# OBCComms.net
KiCad netlist of a schematic drawn in Altium Designer
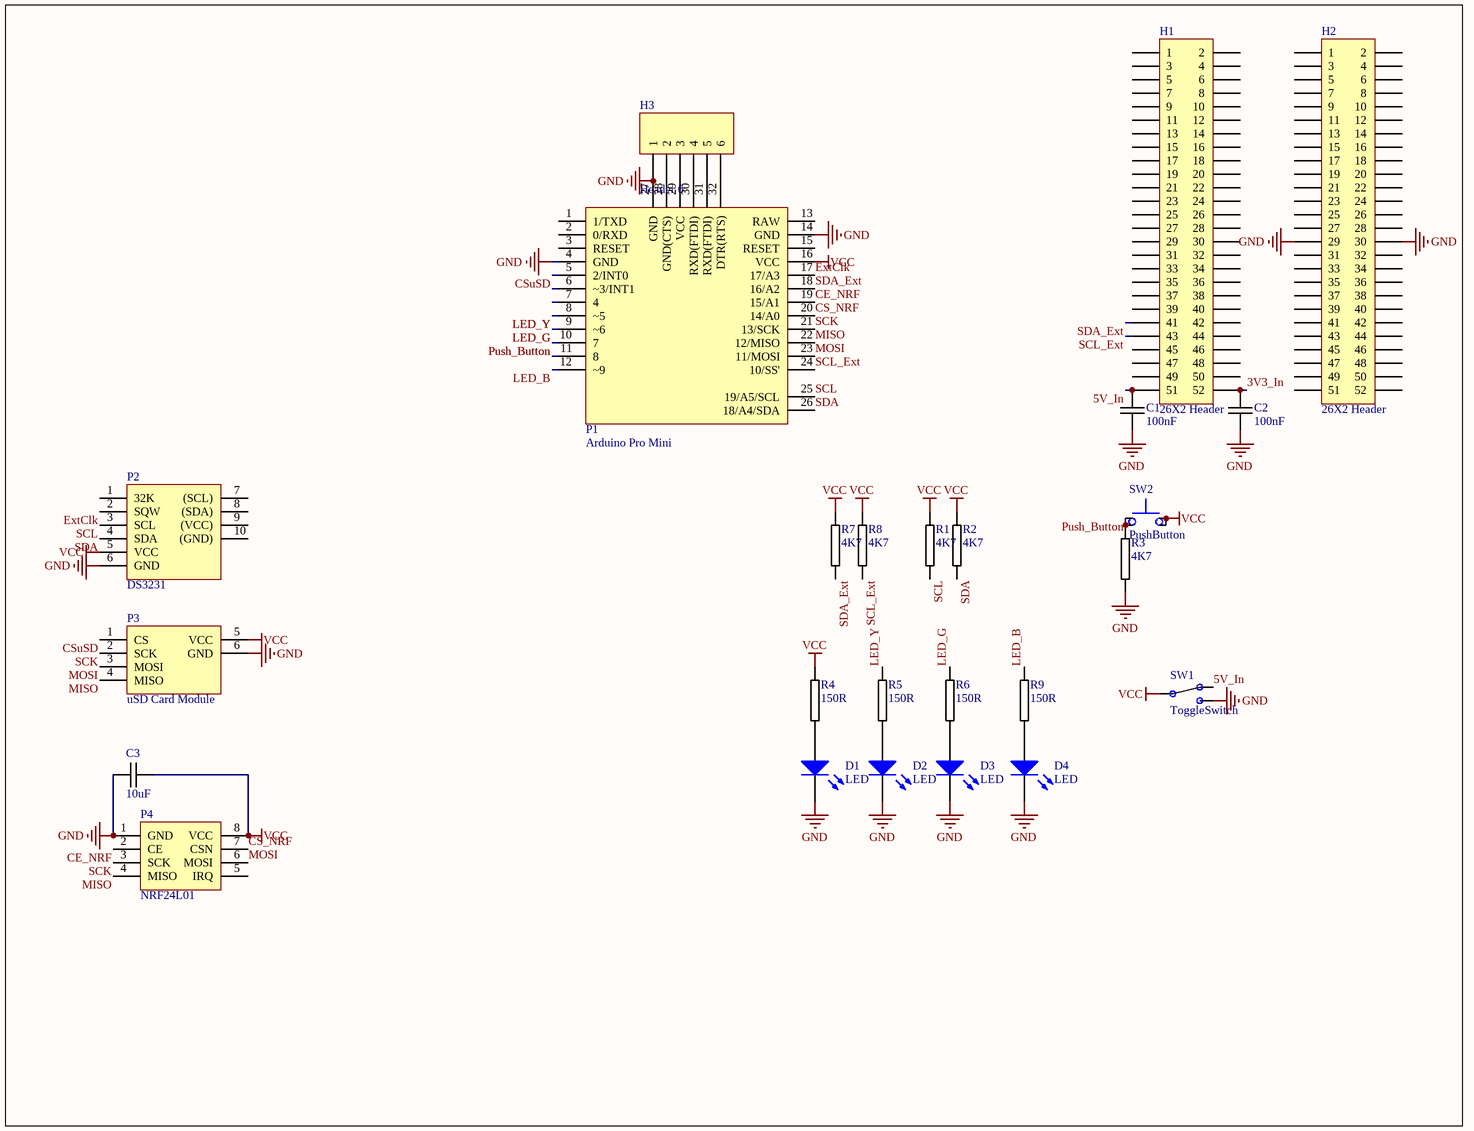
[diagram p0: OBCComms.SchDoc]

(export (version "E")
  (design (tool "Eeschema 10.0.6"))
  (components
    (comp (ref "C1")
      (value "100nF")
      (footprint "0805C-TBD")
      (description "CAPACITOR 0805 CERAMIC")
      (libsource (lib "vh_altium_library") (part "0805C-100nF-25V-X7R-MUR"))
    )
    (comp (ref "C2")
      (value "100nF")
      (footprint "0805C-TBD")
      (description "CAPACITOR 0805 CERAMIC")
      (libsource (lib "vh_altium_library") (part "0805C-100nF-25V-X7R-MUR"))
    )
    (comp (ref "C3")
      (value "10uF")
      (footprint "0805C-GENERIC")
      (description "CAPACITOR 0805 CERAMIC")
      (fields
        (field (name "MANUFACTURER PART NUMBER") "C2012X5R1C106M")
        (field (name "MANUFACTURER") "TDK Corporation")
      )
      (libsource (lib "vh_altium_library") (part "0805C-10UF-16V-X5R-TDK"))
    )
    (comp (ref "D1")
      (value "LED")
      (footprint "LED")
      (description "Small LED")
      (libsource (lib "Components") (part "LED"))
    )
    (comp (ref "D2")
      (value "LED")
      (footprint "LED")
      (description "Small LED")
      (libsource (lib "Components") (part "LED"))
    )
    (comp (ref "D3")
      (value "LED")
      (footprint "LED")
      (description "Small LED")
      (libsource (lib "Components") (part "LED"))
    )
    (comp (ref "D4")
      (value "LED")
      (footprint "LED")
      (description "Small LED")
      (libsource (lib "Components") (part "LED"))
    )
    (comp (ref "H1")
      (value "26X2 Header")
      (footprint "26X2 Header")
      (libsource (lib "CustomParts") (part "26X2 Header"))
    )
    (comp (ref "H2")
      (value "26X2 Header")
      (footprint "26X2 Header")
      (libsource (lib "CustomParts") (part "26X2 Header"))
    )
    (comp (ref "H3")
      (value "Header 6")
      (footprint "HDR1X6")
      (description "Header, 6-Pin")
      (fields (field (name "PUBLISHER") "Altium Limited"))
      (libsource (lib "Miscellaneous Connectors") (part "Header 6"))
    )
    (comp (ref "P1")
      (value "Arduino Pro Mini")
      (footprint "Arduino Pro Mini")
      (libsource (lib "Components") (part "Arduino Pro Mini"))
    )
    (comp (ref "P2")
      (value "DS3231")
      (footprint "RTC")
      (description "RTC")
      (libsource (lib "Components") (part "DS3231"))
    )
    (comp (ref "P3")
      (value "uSD Card Module")
      (footprint "uSD Card Module")
      (libsource (lib "Components") (part "uSD Card Module"))
    )
    (comp (ref "P4")
      (value "NRF24L01")
      (footprint "NRF24L01")
      (description "Radio Transceiver")
      (libsource (lib "Components") (part "NRF24L01"))
    )
    (comp (ref "R1")
      (value "4K7")
      (footprint "0805R-4K7")
      (description "RESISTOR 0805 1/4 WATT THIN FILM")
      (libsource (lib "vh_altium_library") (part "0805R-4K7"))
    )
    (comp (ref "R2")
      (value "4K7")
      (footprint "0805R-4K7")
      (description "RESISTOR 0805 1/4 WATT THIN FILM")
      (libsource (lib "vh_altium_library") (part "0805R-4K7"))
    )
    (comp (ref "R3")
      (value "4K7")
      (footprint "0805R-4K7")
      (description "RESISTOR 0805 1/4 WATT THIN FILM")
      (libsource (lib "vh_altium_library") (part "0805R-4K7"))
    )
    (comp (ref "R4")
      (value "150R")
      (footprint "0805R-150")
      (description "RESISTOR 0805 1/4 WATT THIN FILM")
      (libsource (lib "vh_altium_library") (part "0805R-150"))
    )
    (comp (ref "R5")
      (value "150R")
      (footprint "0805R-150")
      (description "RESISTOR 0805 1/4 WATT THIN FILM")
      (libsource (lib "vh_altium_library") (part "0805R-150"))
    )
    (comp (ref "R6")
      (value "150R")
      (footprint "0805R-150")
      (description "RESISTOR 0805 1/4 WATT THIN FILM")
      (libsource (lib "vh_altium_library") (part "0805R-150"))
    )
    (comp (ref "R7")
      (value "4K7")
      (footprint "0805R-4K7")
      (description "RESISTOR 0805 1/4 WATT THIN FILM")
      (libsource (lib "vh_altium_library") (part "0805R-4K7"))
    )
    (comp (ref "R8")
      (value "4K7")
      (footprint "0805R-4K7")
      (description "RESISTOR 0805 1/4 WATT THIN FILM")
      (libsource (lib "vh_altium_library") (part "0805R-4K7"))
    )
    (comp (ref "R9")
      (value "150R")
      (footprint "0805R-150")
      (description "RESISTOR 0805 1/4 WATT THIN FILM")
      (libsource (lib "vh_altium_library") (part "0805R-150"))
    )
    (comp (ref "SW1")
      (value "ToggleSwitch")
      (footprint "SWITCHFOOTPRINT")
      (libsource (lib "SBv1Components") (part "ToggleSwitch"))
    )
    (comp (ref "SW2")
      (value "PushButton")
      (footprint "PushButton")
      (libsource (lib "SBv1Components") (part "PushButton"))
    )
  )
  (nets
    (net (code "1") (name "/3V3_In") (class "Default")
      (node (ref "C2") (pin "1") (pintype "passive"))
      (node (ref "H1") (pin "52") (pinfunction "52_52") (pintype "passive"))
    )
    (net (code "2") (name "/5V_In") (class "Default")
      (node (ref "C1") (pin "1") (pintype "passive"))
      (node (ref "H1") (pin "51") (pinfunction "51_51") (pintype "passive"))
      (node (ref "SW1") (pin "24") (pinfunction "24_24") (pintype "passive"))
    )
    (net (code "3") (name "/CE_NRF") (class "Default")
      (node (ref "P1") (pin "19") (pinfunction "15/A1_19") (pintype "passive"))
      (node (ref "P4") (pin "2") (pinfunction "CE_2") (pintype "passive"))
    )
    (net (code "4") (name "/CS_NRF") (class "Default")
      (node (ref "P1") (pin "20") (pinfunction "14/A0_20") (pintype "passive"))
      (node (ref "P4") (pin "7") (pinfunction "CSN_7") (pintype "passive"))
    )
    (net (code "5") (name "/CSuSD") (class "Default")
      (node (ref "P1") (pin "5") (pinfunction "2/INT0_5") (pintype "passive"))
      (node (ref "P3") (pin "1") (pinfunction "CS_1") (pintype "passive"))
    )
    (net (code "6") (name "/ExtClk") (class "Default")
      (node (ref "P1") (pin "17") (pinfunction "17/A3_17") (pintype "passive"))
      (node (ref "P2") (pin "2") (pinfunction "SQW_2") (pintype "passive"))
    )
    (net (code "7") (name "/LED_B") (class "Default")
      (node (ref "P1") (pin "12") (pinfunction "~9_12") (pintype "passive"))
      (node (ref "R9") (pin "1") (pintype "passive"))
    )
    (net (code "8") (name "/LED_G") (class "Default")
      (node (ref "P1") (pin "9") (pinfunction "~6_9") (pintype "passive"))
      (node (ref "R6") (pin "1") (pintype "passive"))
    )
    (net (code "9") (name "/LED_Y") (class "Default")
      (node (ref "P1") (pin "8") (pinfunction "~5_8") (pintype "passive"))
      (node (ref "R5") (pin "1") (pintype "passive"))
    )
    (net (code "10") (name "/MISO") (class "Default")
      (node (ref "P1") (pin "22") (pinfunction "12/MISO_22") (pintype "passive"))
      (node (ref "P3") (pin "4") (pinfunction "MISO_4") (pintype "passive"))
      (node (ref "P4") (pin "4") (pinfunction "MISO_4") (pintype "passive"))
    )
    (net (code "11") (name "/MOSI") (class "Default")
      (node (ref "P1") (pin "23") (pinfunction "11/MOSI_23") (pintype "passive"))
      (node (ref "P3") (pin "3") (pinfunction "MOSI_3") (pintype "passive"))
      (node (ref "P4") (pin "6") (pinfunction "MOSI_6") (pintype "passive"))
    )
    (net (code "12") (name "/Push_Button") (class "Default")
      (node (ref "P1") (pin "10") (pinfunction "7_10") (pintype "passive"))
      (node (ref "R3") (pin "1") (pintype "passive"))
      (node (ref "SW2") (pin "26") (pinfunction "26_26") (pintype "passive"))
      (node (ref "SW2") (pin "28") (pinfunction "28_28") (pintype "passive"))
    )
    (net (code "13") (name "/SCK") (class "Default")
      (node (ref "P1") (pin "21") (pinfunction "13/SCK_21") (pintype "passive"))
      (node (ref "P3") (pin "2") (pinfunction "SCK_2") (pintype "passive"))
      (node (ref "P4") (pin "3") (pinfunction "SCK_3") (pintype "passive"))
    )
    (net (code "14") (name "/SCL") (class "Default")
      (node (ref "P1") (pin "25") (pinfunction "19/A5/SCL_25") (pintype "passive"))
      (node (ref "P2") (pin "3") (pinfunction "SCL_3") (pintype "passive"))
      (node (ref "R1") (pin "2") (pintype "passive"))
    )
    (net (code "15") (name "/SCL_Ext") (class "Default")
      (node (ref "H1") (pin "43") (pinfunction "43_43") (pintype "passive"))
      (node (ref "P1") (pin "24") (pinfunction "10/SS'_24") (pintype "passive"))
      (node (ref "R8") (pin "2") (pintype "passive"))
    )
    (net (code "16") (name "/SDA") (class "Default")
      (node (ref "P1") (pin "26") (pinfunction "18/A4/SDA_26") (pintype "passive"))
      (node (ref "P2") (pin "4") (pinfunction "SDA_4") (pintype "passive"))
      (node (ref "R2") (pin "2") (pintype "passive"))
    )
    (net (code "17") (name "/SDA_Ext") (class "Default")
      (node (ref "H1") (pin "41") (pinfunction "41_41") (pintype "passive"))
      (node (ref "P1") (pin "18") (pinfunction "16/A2_18") (pintype "passive"))
      (node (ref "R7") (pin "2") (pintype "passive"))
    )
    (net (code "18") (name "GND") (class "Default")
      (node (ref "C1") (pin "2") (pintype "passive"))
      (node (ref "C2") (pin "2") (pintype "passive"))
      (node (ref "C3") (pin "1") (pintype "passive"))
      (node (ref "D1") (pin "2") (pinfunction "K_2") (pintype "passive"))
      (node (ref "D2") (pin "2") (pinfunction "K_2") (pintype "passive"))
      (node (ref "D3") (pin "2") (pinfunction "K_2") (pintype "passive"))
      (node (ref "D4") (pin "2") (pinfunction "K_2") (pintype "passive"))
      (node (ref "H2") (pin "29") (pinfunction "29_29") (pintype "passive"))
      (node (ref "H2") (pin "30") (pinfunction "30_30") (pintype "passive"))
      (node (ref "H3") (pin "1") (pinfunction "1_1") (pintype "passive"))
      (node (ref "P1") (pin "14") (pinfunction "GND_14") (pintype "passive"))
      (node (ref "P1") (pin "27") (pinfunction "GND_27") (pintype "passive"))
      (node (ref "P1") (pin "4") (pinfunction "GND_4") (pintype "passive"))
      (node (ref "P2") (pin "6") (pinfunction "GND_6") (pintype "passive"))
      (node (ref "P3") (pin "6") (pinfunction "GND_6") (pintype "passive"))
      (node (ref "P4") (pin "1") (pinfunction "GND_1") (pintype "passive"))
      (node (ref "R3") (pin "2") (pintype "passive"))
      (node (ref "SW1") (pin "25") (pinfunction "25_25") (pintype "passive"))
    )
    (net (code "19") (name "Net-(D1-A)") (class "Default")
      (node (ref "D1") (pin "1") (pinfunction "A_1") (pintype "passive"))
      (node (ref "R4") (pin "2") (pintype "passive"))
    )
    (net (code "20") (name "Net-(D2-A)") (class "Default")
      (node (ref "D2") (pin "1") (pinfunction "A_1") (pintype "passive"))
      (node (ref "R5") (pin "2") (pintype "passive"))
    )
    (net (code "21") (name "Net-(D3-A)") (class "Default")
      (node (ref "D3") (pin "1") (pinfunction "A_1") (pintype "passive"))
      (node (ref "R6") (pin "2") (pintype "passive"))
    )
    (net (code "22") (name "Net-(D4-A)") (class "Default")
      (node (ref "D4") (pin "1") (pinfunction "A_1") (pintype "passive"))
      (node (ref "R9") (pin "2") (pintype "passive"))
    )
    (net (code "23") (name "Net-(H3-Pad3)") (class "Default")
      (node (ref "H3") (pin "3") (pinfunction "3_3") (pintype "passive"))
      (node (ref "P1") (pin "29") (pinfunction "VCC_29") (pintype "passive"))
    )
    (net (code "24") (name "Net-(H3-Pad4)") (class "Default")
      (node (ref "H3") (pin "4") (pinfunction "4_4") (pintype "passive"))
      (node (ref "P1") (pin "30") (pinfunction "RXD(FTDI)_30") (pintype "passive"))
    )
    (net (code "25") (name "Net-(H3-Pad5)") (class "Default")
      (node (ref "H3") (pin "5") (pinfunction "5_5") (pintype "passive"))
      (node (ref "P1") (pin "31") (pinfunction "RXD(FTDI)_31") (pintype "passive"))
    )
    (net (code "26") (name "Net-(P1-DTR(RTS))") (class "Default")
      (node (ref "H3") (pin "6") (pinfunction "6_6") (pintype "passive"))
      (node (ref "P1") (pin "32") (pinfunction "DTR(RTS)_32") (pintype "passive"))
    )
    (net (code "27") (name "Net-(P1-GND(CTS))") (class "Default")
      (node (ref "H3") (pin "2") (pinfunction "2_2") (pintype "passive"))
      (node (ref "P1") (pin "28") (pinfunction "GND(CTS)_28") (pintype "passive"))
    )
    (net (code "28") (name "VCC") (class "Default")
      (node (ref "C3") (pin "2") (pintype "passive"))
      (node (ref "P1") (pin "16") (pinfunction "VCC_16") (pintype "passive"))
      (node (ref "P2") (pin "5") (pinfunction "VCC_5") (pintype "passive"))
      (node (ref "P3") (pin "5") (pinfunction "VCC_5") (pintype "passive"))
      (node (ref "P4") (pin "8") (pinfunction "VCC_8") (pintype "passive"))
      (node (ref "R1") (pin "1") (pintype "passive"))
      (node (ref "R2") (pin "1") (pintype "passive"))
      (node (ref "R4") (pin "1") (pintype "passive"))
      (node (ref "R7") (pin "1") (pintype "passive"))
      (node (ref "R8") (pin "1") (pintype "passive"))
      (node (ref "SW1") (pin "23") (pinfunction "23_23") (pintype "passive"))
      (node (ref "SW2") (pin "27") (pinfunction "27_27") (pintype "passive"))
      (node (ref "SW2") (pin "29") (pinfunction "29_29") (pintype "passive"))
    )
    (net (code "29") (name "unconnected-(H1-Pad1)") (class "Default")
      (node (ref "H1") (pin "1") (pinfunction "1_1") (pintype "passive"))
    )
    (net (code "30") (name "unconnected-(H1-Pad2)") (class "Default")
      (node (ref "H1") (pin "2") (pinfunction "2_2") (pintype "passive"))
    )
    (net (code "31") (name "unconnected-(H1-Pad3)") (class "Default")
      (node (ref "H1") (pin "3") (pinfunction "3_3") (pintype "passive"))
    )
    (net (code "32") (name "unconnected-(H1-Pad4)") (class "Default")
      (node (ref "H1") (pin "4") (pinfunction "4_4") (pintype "passive"))
    )
    (net (code "33") (name "unconnected-(H1-Pad5)") (class "Default")
      (node (ref "H1") (pin "5") (pinfunction "5_5") (pintype "passive"))
    )
    (net (code "34") (name "unconnected-(H1-Pad6)") (class "Default")
      (node (ref "H1") (pin "6") (pinfunction "6_6") (pintype "passive"))
    )
    (net (code "35") (name "unconnected-(H1-Pad7)") (class "Default")
      (node (ref "H1") (pin "7") (pinfunction "7_7") (pintype "passive"))
    )
    (net (code "36") (name "unconnected-(H1-Pad8)") (class "Default")
      (node (ref "H1") (pin "8") (pinfunction "8_8") (pintype "passive"))
    )
    (net (code "37") (name "unconnected-(H1-Pad9)") (class "Default")
      (node (ref "H1") (pin "9") (pinfunction "9_9") (pintype "passive"))
    )
    (net (code "38") (name "unconnected-(H1-Pad10)") (class "Default")
      (node (ref "H1") (pin "10") (pinfunction "10_10") (pintype "passive"))
    )
    (net (code "39") (name "unconnected-(H1-Pad11)") (class "Default")
      (node (ref "H1") (pin "11") (pinfunction "11_11") (pintype "passive"))
    )
    (net (code "40") (name "unconnected-(H1-Pad12)") (class "Default")
      (node (ref "H1") (pin "12") (pinfunction "12_12") (pintype "passive"))
    )
    (net (code "41") (name "unconnected-(H1-Pad13)") (class "Default")
      (node (ref "H1") (pin "13") (pinfunction "13_13") (pintype "passive"))
    )
    (net (code "42") (name "unconnected-(H1-Pad14)") (class "Default")
      (node (ref "H1") (pin "14") (pinfunction "14_14") (pintype "passive"))
    )
    (net (code "43") (name "unconnected-(H1-Pad15)") (class "Default")
      (node (ref "H1") (pin "15") (pinfunction "15_15") (pintype "passive"))
    )
    (net (code "44") (name "unconnected-(H1-Pad16)") (class "Default")
      (node (ref "H1") (pin "16") (pinfunction "16_16") (pintype "passive"))
    )
    (net (code "45") (name "unconnected-(H1-Pad17)") (class "Default")
      (node (ref "H1") (pin "17") (pinfunction "17_17") (pintype "passive"))
    )
    (net (code "46") (name "unconnected-(H1-Pad18)") (class "Default")
      (node (ref "H1") (pin "18") (pinfunction "18_18") (pintype "passive"))
    )
    (net (code "47") (name "unconnected-(H1-Pad19)") (class "Default")
      (node (ref "H1") (pin "19") (pinfunction "19_19") (pintype "passive"))
    )
    (net (code "48") (name "unconnected-(H1-Pad20)") (class "Default")
      (node (ref "H1") (pin "20") (pinfunction "20_20") (pintype "passive"))
    )
    (net (code "49") (name "unconnected-(H1-Pad21)") (class "Default")
      (node (ref "H1") (pin "21") (pinfunction "21_21") (pintype "passive"))
    )
    (net (code "50") (name "unconnected-(H1-Pad22)") (class "Default")
      (node (ref "H1") (pin "22") (pinfunction "22_22") (pintype "passive"))
    )
    (net (code "51") (name "unconnected-(H1-Pad23)") (class "Default")
      (node (ref "H1") (pin "23") (pinfunction "23_23") (pintype "passive"))
    )
    (net (code "52") (name "unconnected-(H1-Pad24)") (class "Default")
      (node (ref "H1") (pin "24") (pinfunction "24_24") (pintype "passive"))
    )
    (net (code "53") (name "unconnected-(H1-Pad25)") (class "Default")
      (node (ref "H1") (pin "25") (pinfunction "25_25") (pintype "passive"))
    )
    (net (code "54") (name "unconnected-(H1-Pad26)") (class "Default")
      (node (ref "H1") (pin "26") (pinfunction "26_26") (pintype "passive"))
    )
    (net (code "55") (name "unconnected-(H1-Pad27)") (class "Default")
      (node (ref "H1") (pin "27") (pinfunction "27_27") (pintype "passive"))
    )
    (net (code "56") (name "unconnected-(H1-Pad28)") (class "Default")
      (node (ref "H1") (pin "28") (pinfunction "28_28") (pintype "passive"))
    )
    (net (code "57") (name "unconnected-(H1-Pad29)") (class "Default")
      (node (ref "H1") (pin "29") (pinfunction "29_29") (pintype "passive"))
    )
    (net (code "58") (name "unconnected-(H1-Pad30)") (class "Default")
      (node (ref "H1") (pin "30") (pinfunction "30_30") (pintype "passive"))
    )
    (net (code "59") (name "unconnected-(H1-Pad31)") (class "Default")
      (node (ref "H1") (pin "31") (pinfunction "31_31") (pintype "passive"))
    )
    (net (code "60") (name "unconnected-(H1-Pad32)") (class "Default")
      (node (ref "H1") (pin "32") (pinfunction "32_32") (pintype "passive"))
    )
    (net (code "61") (name "unconnected-(H1-Pad33)") (class "Default")
      (node (ref "H1") (pin "33") (pinfunction "33_33") (pintype "passive"))
    )
    (net (code "62") (name "unconnected-(H1-Pad34)") (class "Default")
      (node (ref "H1") (pin "34") (pinfunction "34_34") (pintype "passive"))
    )
    (net (code "63") (name "unconnected-(H1-Pad35)") (class "Default")
      (node (ref "H1") (pin "35") (pinfunction "35_35") (pintype "passive"))
    )
    (net (code "64") (name "unconnected-(H1-Pad36)") (class "Default")
      (node (ref "H1") (pin "36") (pinfunction "36_36") (pintype "passive"))
    )
    (net (code "65") (name "unconnected-(H1-Pad37)") (class "Default")
      (node (ref "H1") (pin "37") (pinfunction "37_37") (pintype "passive"))
    )
    (net (code "66") (name "unconnected-(H1-Pad38)") (class "Default")
      (node (ref "H1") (pin "38") (pinfunction "38_38") (pintype "passive"))
    )
    (net (code "67") (name "unconnected-(H1-Pad39)") (class "Default")
      (node (ref "H1") (pin "39") (pinfunction "39_39") (pintype "passive"))
    )
    (net (code "68") (name "unconnected-(H1-Pad40)") (class "Default")
      (node (ref "H1") (pin "40") (pinfunction "40_40") (pintype "passive"))
    )
    (net (code "69") (name "unconnected-(H1-Pad42)") (class "Default")
      (node (ref "H1") (pin "42") (pinfunction "42_42") (pintype "passive"))
    )
    (net (code "70") (name "unconnected-(H1-Pad44)") (class "Default")
      (node (ref "H1") (pin "44") (pinfunction "44_44") (pintype "passive"))
    )
    (net (code "71") (name "unconnected-(H1-Pad45)") (class "Default")
      (node (ref "H1") (pin "45") (pinfunction "45_45") (pintype "passive"))
    )
    (net (code "72") (name "unconnected-(H1-Pad46)") (class "Default")
      (node (ref "H1") (pin "46") (pinfunction "46_46") (pintype "passive"))
    )
    (net (code "73") (name "unconnected-(H1-Pad47)") (class "Default")
      (node (ref "H1") (pin "47") (pinfunction "47_47") (pintype "passive"))
    )
    (net (code "74") (name "unconnected-(H1-Pad48)") (class "Default")
      (node (ref "H1") (pin "48") (pinfunction "48_48") (pintype "passive"))
    )
    (net (code "75") (name "unconnected-(H1-Pad49)") (class "Default")
      (node (ref "H1") (pin "49") (pinfunction "49_49") (pintype "passive"))
    )
    (net (code "76") (name "unconnected-(H1-Pad50)") (class "Default")
      (node (ref "H1") (pin "50") (pinfunction "50_50") (pintype "passive"))
    )
    (net (code "77") (name "unconnected-(H2-Pad1)") (class "Default")
      (node (ref "H2") (pin "1") (pinfunction "1_1") (pintype "passive"))
    )
    (net (code "78") (name "unconnected-(H2-Pad2)") (class "Default")
      (node (ref "H2") (pin "2") (pinfunction "2_2") (pintype "passive"))
    )
    (net (code "79") (name "unconnected-(H2-Pad3)") (class "Default")
      (node (ref "H2") (pin "3") (pinfunction "3_3") (pintype "passive"))
    )
    (net (code "80") (name "unconnected-(H2-Pad4)") (class "Default")
      (node (ref "H2") (pin "4") (pinfunction "4_4") (pintype "passive"))
    )
    (net (code "81") (name "unconnected-(H2-Pad5)") (class "Default")
      (node (ref "H2") (pin "5") (pinfunction "5_5") (pintype "passive"))
    )
    (net (code "82") (name "unconnected-(H2-Pad6)") (class "Default")
      (node (ref "H2") (pin "6") (pinfunction "6_6") (pintype "passive"))
    )
    (net (code "83") (name "unconnected-(H2-Pad7)") (class "Default")
      (node (ref "H2") (pin "7") (pinfunction "7_7") (pintype "passive"))
    )
    (net (code "84") (name "unconnected-(H2-Pad8)") (class "Default")
      (node (ref "H2") (pin "8") (pinfunction "8_8") (pintype "passive"))
    )
    (net (code "85") (name "unconnected-(H2-Pad9)") (class "Default")
      (node (ref "H2") (pin "9") (pinfunction "9_9") (pintype "passive"))
    )
    (net (code "86") (name "unconnected-(H2-Pad10)") (class "Default")
      (node (ref "H2") (pin "10") (pinfunction "10_10") (pintype "passive"))
    )
    (net (code "87") (name "unconnected-(H2-Pad11)") (class "Default")
      (node (ref "H2") (pin "11") (pinfunction "11_11") (pintype "passive"))
    )
    (net (code "88") (name "unconnected-(H2-Pad12)") (class "Default")
      (node (ref "H2") (pin "12") (pinfunction "12_12") (pintype "passive"))
    )
    (net (code "89") (name "unconnected-(H2-Pad13)") (class "Default")
      (node (ref "H2") (pin "13") (pinfunction "13_13") (pintype "passive"))
    )
    (net (code "90") (name "unconnected-(H2-Pad14)") (class "Default")
      (node (ref "H2") (pin "14") (pinfunction "14_14") (pintype "passive"))
    )
    (net (code "91") (name "unconnected-(H2-Pad15)") (class "Default")
      (node (ref "H2") (pin "15") (pinfunction "15_15") (pintype "passive"))
    )
    (net (code "92") (name "unconnected-(H2-Pad16)") (class "Default")
      (node (ref "H2") (pin "16") (pinfunction "16_16") (pintype "passive"))
    )
    (net (code "93") (name "unconnected-(H2-Pad17)") (class "Default")
      (node (ref "H2") (pin "17") (pinfunction "17_17") (pintype "passive"))
    )
    (net (code "94") (name "unconnected-(H2-Pad18)") (class "Default")
      (node (ref "H2") (pin "18") (pinfunction "18_18") (pintype "passive"))
    )
    (net (code "95") (name "unconnected-(H2-Pad19)") (class "Default")
      (node (ref "H2") (pin "19") (pinfunction "19_19") (pintype "passive"))
    )
    (net (code "96") (name "unconnected-(H2-Pad20)") (class "Default")
      (node (ref "H2") (pin "20") (pinfunction "20_20") (pintype "passive"))
    )
    (net (code "97") (name "unconnected-(H2-Pad21)") (class "Default")
      (node (ref "H2") (pin "21") (pinfunction "21_21") (pintype "passive"))
    )
    (net (code "98") (name "unconnected-(H2-Pad22)") (class "Default")
      (node (ref "H2") (pin "22") (pinfunction "22_22") (pintype "passive"))
    )
    (net (code "99") (name "unconnected-(H2-Pad23)") (class "Default")
      (node (ref "H2") (pin "23") (pinfunction "23_23") (pintype "passive"))
    )
    (net (code "100") (name "unconnected-(H2-Pad24)") (class "Default")
      (node (ref "H2") (pin "24") (pinfunction "24_24") (pintype "passive"))
    )
    (net (code "101") (name "unconnected-(H2-Pad25)") (class "Default")
      (node (ref "H2") (pin "25") (pinfunction "25_25") (pintype "passive"))
    )
    (net (code "102") (name "unconnected-(H2-Pad26)") (class "Default")
      (node (ref "H2") (pin "26") (pinfunction "26_26") (pintype "passive"))
    )
    (net (code "103") (name "unconnected-(H2-Pad27)") (class "Default")
      (node (ref "H2") (pin "27") (pinfunction "27_27") (pintype "passive"))
    )
    (net (code "104") (name "unconnected-(H2-Pad28)") (class "Default")
      (node (ref "H2") (pin "28") (pinfunction "28_28") (pintype "passive"))
    )
    (net (code "105") (name "unconnected-(H2-Pad31)") (class "Default")
      (node (ref "H2") (pin "31") (pinfunction "31_31") (pintype "passive"))
    )
    (net (code "106") (name "unconnected-(H2-Pad32)") (class "Default")
      (node (ref "H2") (pin "32") (pinfunction "32_32") (pintype "passive"))
    )
    (net (code "107") (name "unconnected-(H2-Pad33)") (class "Default")
      (node (ref "H2") (pin "33") (pinfunction "33_33") (pintype "passive"))
    )
    (net (code "108") (name "unconnected-(H2-Pad34)") (class "Default")
      (node (ref "H2") (pin "34") (pinfunction "34_34") (pintype "passive"))
    )
    (net (code "109") (name "unconnected-(H2-Pad35)") (class "Default")
      (node (ref "H2") (pin "35") (pinfunction "35_35") (pintype "passive"))
    )
    (net (code "110") (name "unconnected-(H2-Pad36)") (class "Default")
      (node (ref "H2") (pin "36") (pinfunction "36_36") (pintype "passive"))
    )
    (net (code "111") (name "unconnected-(H2-Pad37)") (class "Default")
      (node (ref "H2") (pin "37") (pinfunction "37_37") (pintype "passive"))
    )
    (net (code "112") (name "unconnected-(H2-Pad38)") (class "Default")
      (node (ref "H2") (pin "38") (pinfunction "38_38") (pintype "passive"))
    )
    (net (code "113") (name "unconnected-(H2-Pad39)") (class "Default")
      (node (ref "H2") (pin "39") (pinfunction "39_39") (pintype "passive"))
    )
    (net (code "114") (name "unconnected-(H2-Pad40)") (class "Default")
      (node (ref "H2") (pin "40") (pinfunction "40_40") (pintype "passive"))
    )
    (net (code "115") (name "unconnected-(H2-Pad41)") (class "Default")
      (node (ref "H2") (pin "41") (pinfunction "41_41") (pintype "passive"))
    )
    (net (code "116") (name "unconnected-(H2-Pad42)") (class "Default")
      (node (ref "H2") (pin "42") (pinfunction "42_42") (pintype "passive"))
    )
    (net (code "117") (name "unconnected-(H2-Pad43)") (class "Default")
      (node (ref "H2") (pin "43") (pinfunction "43_43") (pintype "passive"))
    )
    (net (code "118") (name "unconnected-(H2-Pad44)") (class "Default")
      (node (ref "H2") (pin "44") (pinfunction "44_44") (pintype "passive"))
    )
    (net (code "119") (name "unconnected-(H2-Pad45)") (class "Default")
      (node (ref "H2") (pin "45") (pinfunction "45_45") (pintype "passive"))
    )
    (net (code "120") (name "unconnected-(H2-Pad46)") (class "Default")
      (node (ref "H2") (pin "46") (pinfunction "46_46") (pintype "passive"))
    )
    (net (code "121") (name "unconnected-(H2-Pad47)") (class "Default")
      (node (ref "H2") (pin "47") (pinfunction "47_47") (pintype "passive"))
    )
    (net (code "122") (name "unconnected-(H2-Pad48)") (class "Default")
      (node (ref "H2") (pin "48") (pinfunction "48_48") (pintype "passive"))
    )
    (net (code "123") (name "unconnected-(H2-Pad49)") (class "Default")
      (node (ref "H2") (pin "49") (pinfunction "49_49") (pintype "passive"))
    )
    (net (code "124") (name "unconnected-(H2-Pad50)") (class "Default")
      (node (ref "H2") (pin "50") (pinfunction "50_50") (pintype "passive"))
    )
    (net (code "125") (name "unconnected-(H2-Pad51)") (class "Default")
      (node (ref "H2") (pin "51") (pinfunction "51_51") (pintype "passive"))
    )
    (net (code "126") (name "unconnected-(H2-Pad52)") (class "Default")
      (node (ref "H2") (pin "52") (pinfunction "52_52") (pintype "passive"))
    )
    (net (code "127") (name "unconnected-(P1-0{slash}RXD-Pad2)") (class "Default")
      (node (ref "P1") (pin "2") (pinfunction "0/RXD_2") (pintype "passive"))
    )
    (net (code "128") (name "unconnected-(P1-1{slash}TXD-Pad1)") (class "Default")
      (node (ref "P1") (pin "1") (pinfunction "1/TXD_1") (pintype "passive"))
    )
    (net (code "129") (name "unconnected-(P1-4-Pad7)") (class "Default")
      (node (ref "P1") (pin "7") (pinfunction "4_7") (pintype "passive"))
    )
    (net (code "130") (name "unconnected-(P1-8-Pad11)") (class "Default")
      (node (ref "P1") (pin "11") (pinfunction "8_11") (pintype "passive"))
    )
    (net (code "131") (name "unconnected-(P1-RAW-Pad13)") (class "Default")
      (node (ref "P1") (pin "13") (pinfunction "RAW_13") (pintype "passive"))
    )
    (net (code "132") (name "unconnected-(P1-RESET-Pad3)") (class "Default")
      (node (ref "P1") (pin "3") (pinfunction "RESET_3") (pintype "passive"))
    )
    (net (code "133") (name "unconnected-(P1-RESET-Pad15)") (class "Default")
      (node (ref "P1") (pin "15") (pinfunction "RESET_15") (pintype "passive"))
    )
    (net (code "134") (name "unconnected-(P1-~3{slash}INT1-Pad6)") (class "Default")
      (node (ref "P1") (pin "6") (pinfunction "~3/INT1_6") (pintype "passive"))
    )
    (net (code "135") (name "unconnected-(P2-(GND)-Pad10)") (class "Default")
      (node (ref "P2") (pin "10") (pinfunction "(GND)_10") (pintype "passive"))
    )
    (net (code "136") (name "unconnected-(P2-(SCL)-Pad7)") (class "Default")
      (node (ref "P2") (pin "7") (pinfunction "(SCL)_7") (pintype "passive"))
    )
    (net (code "137") (name "unconnected-(P2-(SDA)-Pad8)") (class "Default")
      (node (ref "P2") (pin "8") (pinfunction "(SDA)_8") (pintype "passive"))
    )
    (net (code "138") (name "unconnected-(P2-(VCC)-Pad9)") (class "Default")
      (node (ref "P2") (pin "9") (pinfunction "(VCC)_9") (pintype "passive"))
    )
    (net (code "139") (name "unconnected-(P2-32K-Pad1)") (class "Default")
      (node (ref "P2") (pin "1") (pinfunction "32K_1") (pintype "passive"))
    )
    (net (code "140") (name "unconnected-(P4-IRQ-Pad5)") (class "Default")
      (node (ref "P4") (pin "5") (pinfunction "IRQ_5") (pintype "passive"))
    )
  )
)
